# RTC.net
KiCad netlist of a schematic drawn in Altium Designer
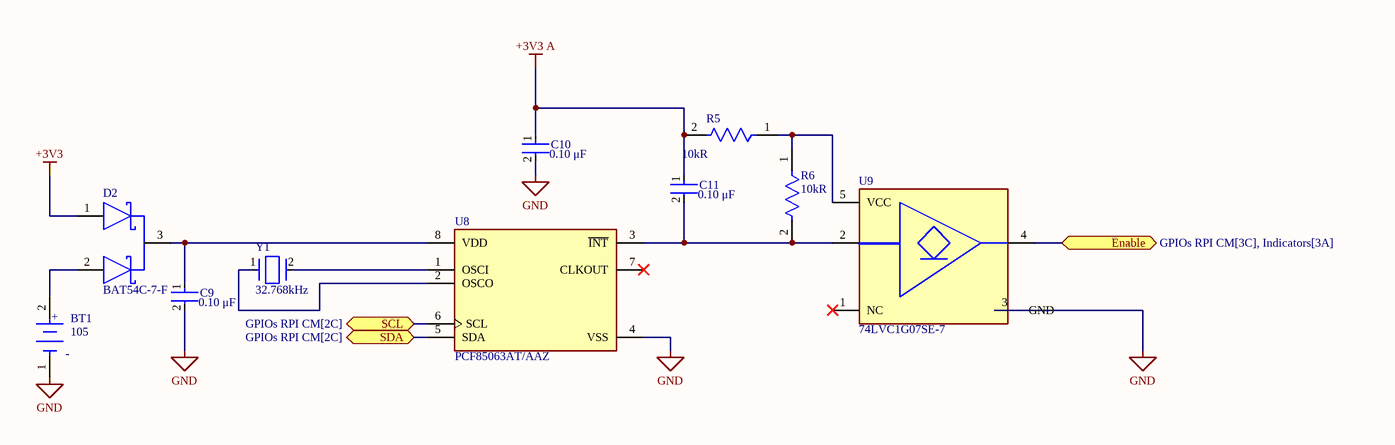
[diagram p0: RTC.SchDoc]

(export (version "E")
  (design (tool "Eeschema 10.0.6"))
  (components
    (comp (ref "BT1")
      (value "105")
      (footprint "FP-105-MFG")
      (description "105 Battery Holder Coin Cell 1 Cell PC Pin PCB Through Hole Mount PBT 0.944 in. Dia")
      (libsource (lib "Altium Content Vault") (part "db879b5662d49c975a5ff8b5862d222"))
    )
    (comp (ref "C9")
      (value "C0402C104K8PACTU")
      (footprint "FP-C0402-BB-IPC_C")
      (description "CAP CER 0.1UF 10V X5R 0402")
      (fields
        (field (name "CAPACITANCE") "0.10 μF")
        (field (name "MANUFACTURER") "Kemet")
        (field (name "TOLERANCE") "0.1")
      )
      (libsource (lib "Altium Content Vault") (part "b4654b650e69147ec39a6b967a45e02"))
    )
    (comp (ref "C10")
      (value "C0402C104K8PACTU")
      (footprint "FP-C0402-BB-IPC_C")
      (description "CAP CER 0.1UF 10V X5R 0402")
      (fields
        (field (name "CAPACITANCE") "0.10 μF")
        (field (name "MANUFACTURER") "Kemet")
        (field (name "TOLERANCE") "0.1")
      )
      (libsource (lib "Altium Content Vault") (part "b4654b650e69147ec39a6b967a45e02"))
    )
    (comp (ref "C11")
      (value "C0402C104K8PACTU")
      (footprint "FP-C0402-BB-IPC_C")
      (description "CAP CER 0.1UF 10V X5R 0402")
      (fields
        (field (name "CAPACITANCE") "0.10 μF")
        (field (name "MANUFACTURER") "Kemet")
        (field (name "TOLERANCE") "0.1")
      )
      (libsource (lib "Altium Content Vault") (part "b4654b650e69147ec39a6b967a45e02"))
    )
    (comp (ref "D2")
      (value "BAT54C-7-F")
      (footprint "FP-SOT23-IPC_B")
      (description "DIODE ARRAY SCHOTTKY 30V SOT23-3")
      (libsource (lib "Altium Content Vault") (part "3eac2aa0c1ac86323ecc23460aa29c6"))
    )
    (comp (ref "R5")
      (value "RC0603FR-0710KL")
      (footprint "FP-RC0603-0_55-IPC_C")
      (description "RES 10K OHM 1% 1/10W 0603")
      (fields (field (name "TOLERANCE") "1%") (field (name "RESISTANCE") "10kR"))
      (libsource (lib "Altium Content Vault") (part "1029c3af85768c4190bb7ad29bc67b5"))
    )
    (comp (ref "R6")
      (value "RC0603FR-0710KL")
      (footprint "FP-RC0603-0_55-IPC_C")
      (description "RES 10K OHM 1% 1/10W 0603")
      (fields (field (name "TOLERANCE") "1%") (field (name "RESISTANCE") "10kR"))
      (libsource (lib "Altium Content Vault") (part "1029c3af85768c4190bb7ad29bc67b5"))
    )
    (comp (ref "U8")
      (value "PCF85063AT/AAZ")
      (footprint "FP-SOT96-1-MFG")
      (description "IC RTC CLK/CALENDAR I2C 8SOIC")
      (libsource (lib "Altium Content Vault") (part "4dc28abe8360043d43596dd8250e67d"))
    )
    (comp (ref "U9")
      (value "74LVC1G07SE-7")
      (footprint "FP-SOT353-MFG")
      (description "IC BUF NON-INVERT 5.5V SOT353")
      (fields
        (field (name "MANUFACTURER") "Diodes Inc.")
        (field (name "OCTOPART") "https://octopart.com/74lvc1g07se-7-diodes+inc.-18882698")
      )
      (libsource (lib "Altium Content Vault") (part "1af1fa4339a335f25e71eb4dc151592"))
    )
    (comp (ref "Y1")
      (value "ABS07-32.768KHZ-T")
      (footprint "FP-ABS07-MFG")
      (description "Crystal 32.768kHz ±20ppm (Tol) 12.5pF FUND 70kΩ 2-Pin CSMD T/R")
      (fields (field (name "FREQUENCY") "32.768kHz") (field (name "TOLERANCE") "20ppm"))
      (libsource (lib "Altium Content Vault") (part "c23a69dc6c9e2f18f2079038eb95dd1"))
    )
  )
  (nets
    (net (code "1") (name "+3V3") (class "Default")
      (node (ref "D2") (pin "1") (pinfunction "1_ANODE_1") (pintype "passive"))
    )
    (net (code "2") (name "+3V3 A") (class "Default")
      (node (ref "C10") (pin "1") (pinfunction "1_1") (pintype "passive"))
      (node (ref "C11") (pin "1") (pinfunction "1_1") (pintype "passive"))
      (node (ref "R5") (pin "2") (pinfunction "2_2") (pintype "passive"))
    )
    (net (code "3") (name "/Enable") (class "Default")
      (node (ref "U9") (pin "4") (pinfunction "Y_4") (pintype "passive"))
    )
    (net (code "4") (name "/SCL") (class "Default")
      (node (ref "U8") (pin "6") (pinfunction "SCL_6") (pintype "passive"))
    )
    (net (code "5") (name "/SDA") (class "Default")
      (node (ref "U8") (pin "5") (pinfunction "SDA_5") (pintype "passive"))
    )
    (net (code "6") (name "GND") (class "Default")
      (node (ref "BT1") (pin "1") (pinfunction "-_1") (pintype "passive"))
      (node (ref "C10") (pin "2") (pinfunction "2_2") (pintype "passive"))
      (node (ref "C9") (pin "2") (pinfunction "2_2") (pintype "passive"))
      (node (ref "U8") (pin "4") (pinfunction "VSS_4") (pintype "power_in"))
      (node (ref "U9") (pin "3") (pinfunction "GND_3") (pintype "power_in"))
    )
    (net (code "7") (name "Net-(BT1-+)") (class "Default")
      (node (ref "BT1") (pin "2") (pinfunction "+_2") (pintype "passive"))
      (node (ref "D2") (pin "2") (pinfunction "2_ANODE_2") (pintype "passive"))
    )
    (net (code "8") (name "Net-(D2-COMMON_CATHODE)") (class "Default")
      (node (ref "C9") (pin "1") (pinfunction "1_1") (pintype "passive"))
      (node (ref "D2") (pin "3") (pinfunction "COMMON_CATHODE_3") (pintype "passive"))
      (node (ref "U8") (pin "8") (pinfunction "VDD_8") (pintype "power_in"))
    )
    (net (code "9") (name "Net-(U8-OSCI)") (class "Default")
      (node (ref "U8") (pin "1") (pinfunction "OSCI_1") (pintype "passive"))
      (node (ref "Y1") (pin "2") (pinfunction "2_2") (pintype "passive"))
    )
    (net (code "10") (name "Net-(U8-OSCO)") (class "Default")
      (node (ref "U8") (pin "2") (pinfunction "OSCO_2") (pintype "passive"))
      (node (ref "Y1") (pin "1") (pinfunction "1_1") (pintype "passive"))
    )
    (net (code "11") (name "Net-(U8-~{INT})") (class "Default")
      (node (ref "C11") (pin "2") (pinfunction "2_2") (pintype "passive"))
      (node (ref "R6") (pin "2") (pinfunction "2_2") (pintype "passive"))
      (node (ref "U8") (pin "3") (pinfunction "~{INT}_3") (pintype "passive"))
      (node (ref "U9") (pin "2") (pinfunction "A_2") (pintype "passive"))
    )
    (net (code "12") (name "Net-(U9-VCC)") (class "Default")
      (node (ref "R5") (pin "1") (pinfunction "1_1") (pintype "passive"))
      (node (ref "R6") (pin "1") (pinfunction "1_1") (pintype "passive"))
      (node (ref "U9") (pin "5") (pinfunction "VCC_5") (pintype "power_in"))
    )
    (net (code "13") (name "unconnected-(U8-CLKOUT-Pad7)") (class "Default")
      (node (ref "U8") (pin "7") (pinfunction "CLKOUT_7") (pintype "passive+no_connect"))
    )
    (net (code "14") (name "unconnected-(U9-NC-Pad1)") (class "Default")
      (node (ref "U9") (pin "1") (pinfunction "NC_1") (pintype "passive+no_connect"))
    )
  )
)
